# control-zenerbridge2.net
KiCad netlist of a schematic drawn in EAGLE
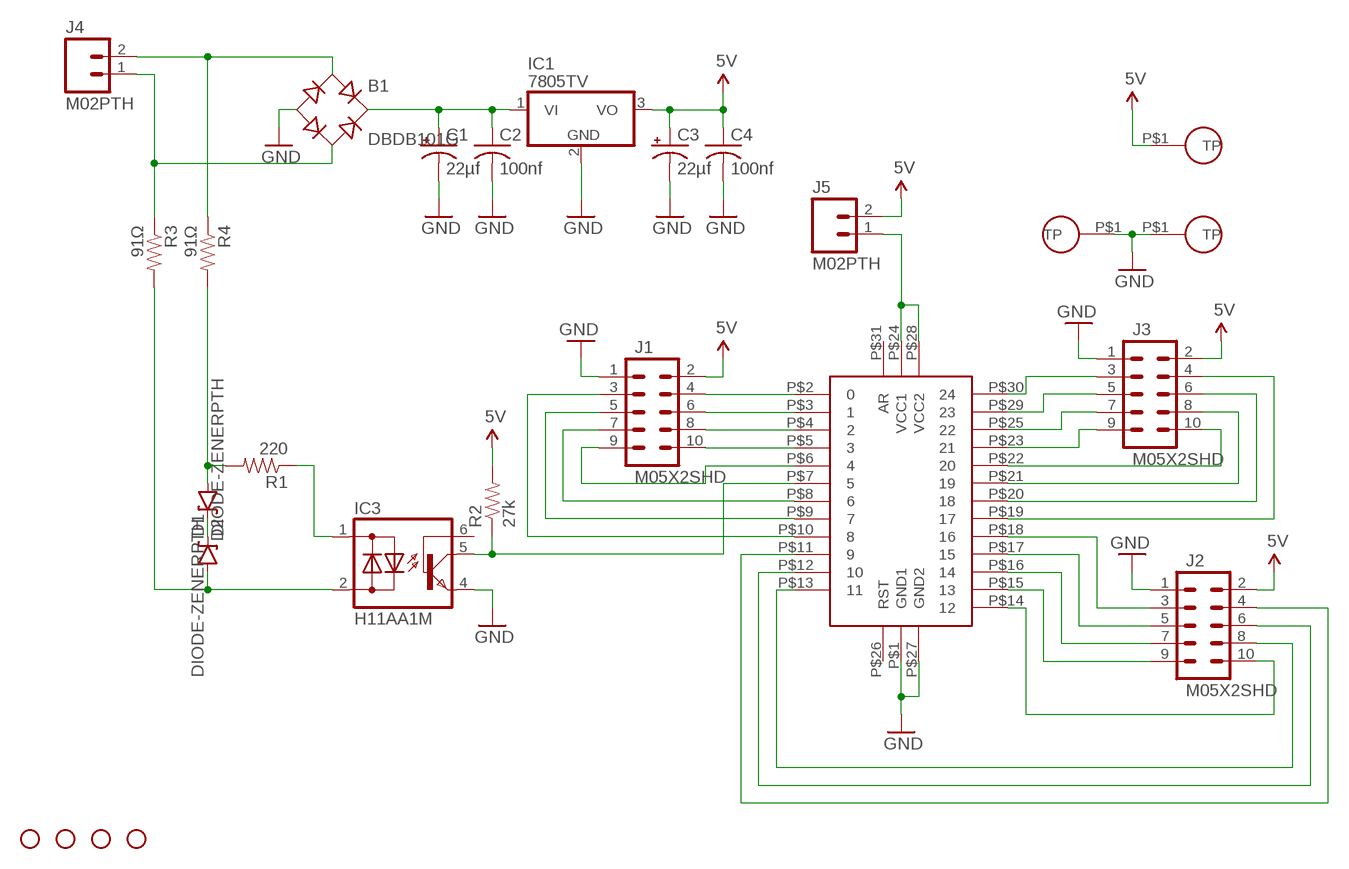
[diagram p0: schematic, sheet 1]

(export (version "E")
  (design (tool "Eeschema 10.0.6"))
  (components
    (comp (ref "B1")
      (value "DBDB101G")
      (footprint "eagle-import:DB")
      (libsource (lib "eagle-import") (part "DB?GDB101"))
    )
    (comp (ref "C1")
      (value "22µf")
      (footprint "eagle-import:E5-8,5")
      (libsource (lib "eagle-import") (part "CPOL-USE5-8.5"))
    )
    (comp (ref "C2")
      (value "100nf")
      (footprint "eagle-import:C025-030X050")
      (libsource (lib "eagle-import") (part "C-US025-030X050"))
    )
    (comp (ref "C3")
      (value "22µf")
      (footprint "eagle-import:E5-8,5")
      (libsource (lib "eagle-import") (part "CPOL-USE5-8.5"))
    )
    (comp (ref "C4")
      (value "100nf")
      (footprint "eagle-import:C025-030X050")
      (libsource (lib "eagle-import") (part "C-US025-030X050"))
    )
    (comp (ref "D1")
      (value "DIODE-ZENERPTH")
      (footprint "eagle-import:DIODE-ZENER")
      (libsource (lib "eagle-import") (part "DIODE-ZENERPTH"))
    )
    (comp (ref "D2")
      (value "DIODE-ZENERPTH")
      (footprint "eagle-import:DIODE-ZENER")
      (libsource (lib "eagle-import") (part "DIODE-ZENERPTH"))
    )
    (comp (ref "IC1")
      (value "7805TV")
      (footprint "eagle-import:TO220V")
      (libsource (lib "eagle-import") (part "78TV05"))
    )
    (comp (ref "IC2")
      (value "TEENSY2")
      (footprint "eagle-import:TEENSY2")
      (libsource (lib "eagle-import") (part "TEENSY2"))
    )
    (comp (ref "IC3")
      (value "H11AA1M")
      (footprint "eagle-import:DIL06")
      (fields (field (name "MF") "Fairchild"))
      (libsource (lib "eagle-import") (part "H11AA1M"))
    )
    (comp (ref "J1")
      (value "M05X2SHD")
      (footprint "eagle-import:2X5-SHROUDED")
      (libsource (lib "eagle-import") (part "M05X2SHD"))
    )
    (comp (ref "J2")
      (value "M05X2SHD")
      (footprint "eagle-import:2X5-SHROUDED")
      (libsource (lib "eagle-import") (part "M05X2SHD"))
    )
    (comp (ref "J3")
      (value "M05X2SHD")
      (footprint "eagle-import:2X5-SHROUDED")
      (libsource (lib "eagle-import") (part "M05X2SHD"))
    )
    (comp (ref "J4")
      (value "M02PTH")
      (footprint "eagle-import:1X02")
      (libsource (lib "eagle-import") (part "M02PTH"))
    )
    (comp (ref "J5")
      (value "M02PTH")
      (footprint "eagle-import:1X02")
      (libsource (lib "eagle-import") (part "M02PTH"))
    )
    (comp (ref "R1")
      (value "220")
      (footprint "eagle-import:AXIAL-0.4")
      (libsource (lib "eagle-import") (part "RESISTORPTH-1/4W"))
    )
    (comp (ref "R2")
      (value "27k")
      (footprint "eagle-import:AXIAL-0.4")
      (libsource (lib "eagle-import") (part "RESISTORPTH-1/4W"))
    )
    (comp (ref "R3")
      (value "91Ω")
      (footprint "eagle-import:AXIAL-0.4")
      (libsource (lib "eagle-import") (part "RESISTORPTH-1/4W"))
    )
    (comp (ref "R4")
      (value "91Ω")
      (footprint "eagle-import:AXIAL-0.4")
      (libsource (lib "eagle-import") (part "RESISTORPTH-1/4W"))
    )
    (comp (ref "STANDOFF1")
      (value "STAND-OFF")
      (footprint "eagle-import:STAND-OFF")
      (libsource (lib "eagle-import") (part "STAND-OFF"))
    )
    (comp (ref "STANDOFF2")
      (value "STAND-OFF")
      (footprint "eagle-import:STAND-OFF")
      (libsource (lib "eagle-import") (part "STAND-OFF"))
    )
    (comp (ref "STANDOFF3")
      (value "STAND-OFF")
      (footprint "eagle-import:STAND-OFF")
      (libsource (lib "eagle-import") (part "STAND-OFF"))
    )
    (comp (ref "STANDOFF4")
      (value "STAND-OFF")
      (footprint "eagle-import:STAND-OFF")
      (libsource (lib "eagle-import") (part "STAND-OFF"))
    )
    (comp (ref "U$3") (value "TP") (footprint "eagle-import:TP") (libsource (lib "eagle-import") (part "TP")))
    (comp (ref "U$8") (value "TP") (footprint "eagle-import:TP") (libsource (lib "eagle-import") (part "TP")))
    (comp (ref "U$9") (value "TP") (footprint "eagle-import:TP") (libsource (lib "eagle-import") (part "TP")))
  )
  (nets
    (net (code "1") (name "5V") (class "Default")
      (node (ref "C3") (pin "+") (pinfunction "+_+") (pintype "passive"))
      (node (ref "C4") (pin "1") (pinfunction "1_1") (pintype "passive"))
      (node (ref "IC1") (pin "3") (pinfunction "VO_3") (pintype "passive"))
      (node (ref "J1") (pin "2") (pinfunction "2_2") (pintype "passive"))
      (node (ref "J2") (pin "2") (pinfunction "2_2") (pintype "passive"))
      (node (ref "J3") (pin "2") (pinfunction "2_2") (pintype "passive"))
      (node (ref "J5") (pin "2") (pinfunction "2_2") (pintype "passive"))
      (node (ref "R2") (pin "P$2") (pinfunction "2_P$2") (pintype "passive"))
      (node (ref "U$8") (pin "P$1") (pinfunction "TP_P$1") (pintype "input"))
    )
    (net (code "2") (name "GND") (class "Default")
      (node (ref "B1") (pin "-") (pinfunction "-_-") (pintype "passive"))
      (node (ref "C1") (pin "-") (pinfunction "-_-") (pintype "passive"))
      (node (ref "C2") (pin "2") (pinfunction "2_2") (pintype "passive"))
      (node (ref "C3") (pin "-") (pinfunction "-_-") (pintype "passive"))
      (node (ref "C4") (pin "2") (pinfunction "2_2") (pintype "passive"))
      (node (ref "IC1") (pin "2") (pinfunction "GND_2") (pintype "passive"))
      (node (ref "IC2") (pin "P$1") (pinfunction "GND1_P$1") (pintype "bidirectional"))
      (node (ref "IC2") (pin "P$27") (pinfunction "GND2_P$27") (pintype "bidirectional"))
      (node (ref "IC3") (pin "4") (pinfunction "E_4") (pintype "passive"))
      (node (ref "J1") (pin "1") (pinfunction "1_1") (pintype "passive"))
      (node (ref "J2") (pin "1") (pinfunction "1_1") (pintype "passive"))
      (node (ref "J3") (pin "1") (pinfunction "1_1") (pintype "passive"))
      (node (ref "U$3") (pin "P$1") (pinfunction "TP_P$1") (pintype "input"))
      (node (ref "U$9") (pin "P$1") (pinfunction "TP_P$1") (pintype "input"))
    )
    (net (code "3") (name "Net-(D1-A)") (class "Default")
      (node (ref "D1") (pin "P$2") (pinfunction "A_P$2") (pintype "passive"))
      (node (ref "IC3") (pin "2") (pinfunction "AC2_2") (pintype "passive"))
      (node (ref "R3") (pin "P$2") (pinfunction "2_P$2") (pintype "passive"))
    )
    (net (code "4") (name "Net-(D1-C)") (class "Default")
      (node (ref "D1") (pin "P$1") (pinfunction "C_P$1") (pintype "passive"))
      (node (ref "D2") (pin "P$1") (pinfunction "C_P$1") (pintype "passive"))
    )
    (net (code "5") (name "Net-(D2-A)") (class "Default")
      (node (ref "D2") (pin "P$2") (pinfunction "A_P$2") (pintype "passive"))
      (node (ref "R1") (pin "P$2") (pinfunction "2_P$2") (pintype "passive"))
      (node (ref "R4") (pin "P$2") (pinfunction "2_P$2") (pintype "passive"))
    )
    (net (code "6") (name "Net-(IC1-VI)") (class "Default")
      (node (ref "B1") (pin "+") (pinfunction "+_+") (pintype "passive"))
      (node (ref "C1") (pin "+") (pinfunction "+_+") (pintype "passive"))
      (node (ref "C2") (pin "1") (pinfunction "1_1") (pintype "passive"))
      (node (ref "IC1") (pin "1") (pinfunction "VI_1") (pintype "input"))
    )
    (net (code "7") (name "Net-(IC2-0)") (class "Default")
      (node (ref "IC2") (pin "P$2") (pinfunction "0_P$2") (pintype "bidirectional"))
      (node (ref "J1") (pin "4") (pinfunction "4_4") (pintype "passive"))
    )
    (net (code "8") (name "Net-(IC2-1)") (class "Default")
      (node (ref "IC2") (pin "P$3") (pinfunction "1_P$3") (pintype "bidirectional"))
      (node (ref "J1") (pin "6") (pinfunction "6_6") (pintype "passive"))
    )
    (net (code "9") (name "Net-(IC2-2)") (class "Default")
      (node (ref "IC2") (pin "P$4") (pinfunction "2_P$4") (pintype "bidirectional"))
      (node (ref "J1") (pin "8") (pinfunction "8_8") (pintype "passive"))
    )
    (net (code "10") (name "Net-(IC2-3)") (class "Default")
      (node (ref "IC2") (pin "P$5") (pinfunction "3_P$5") (pintype "bidirectional"))
      (node (ref "J1") (pin "10") (pinfunction "10_10") (pintype "passive"))
    )
    (net (code "11") (name "Net-(IC2-4)") (class "Default")
      (node (ref "IC2") (pin "P$6") (pinfunction "4_P$6") (pintype "bidirectional"))
      (node (ref "J1") (pin "9") (pinfunction "9_9") (pintype "passive"))
    )
    (net (code "12") (name "Net-(IC2-5)") (class "Default")
      (node (ref "IC2") (pin "P$7") (pinfunction "5_P$7") (pintype "bidirectional"))
      (node (ref "IC3") (pin "5") (pinfunction "C_5") (pintype "passive"))
      (node (ref "R2") (pin "P$1") (pinfunction "1_P$1") (pintype "passive"))
    )
    (net (code "13") (name "Net-(IC2-6)") (class "Default")
      (node (ref "IC2") (pin "P$8") (pinfunction "6_P$8") (pintype "bidirectional"))
      (node (ref "J1") (pin "7") (pinfunction "7_7") (pintype "passive"))
    )
    (net (code "14") (name "Net-(IC2-7)") (class "Default")
      (node (ref "IC2") (pin "P$9") (pinfunction "7_P$9") (pintype "bidirectional"))
      (node (ref "J1") (pin "5") (pinfunction "5_5") (pintype "passive"))
    )
    (net (code "15") (name "Net-(IC2-8)") (class "Default")
      (node (ref "IC2") (pin "P$10") (pinfunction "8_P$10") (pintype "bidirectional"))
      (node (ref "J1") (pin "3") (pinfunction "3_3") (pintype "passive"))
    )
    (net (code "16") (name "Net-(IC2-9)") (class "Default")
      (node (ref "IC2") (pin "P$11") (pinfunction "9_P$11") (pintype "bidirectional"))
      (node (ref "J2") (pin "4") (pinfunction "4_4") (pintype "passive"))
    )
    (net (code "17") (name "Net-(IC2-10)") (class "Default")
      (node (ref "IC2") (pin "P$12") (pinfunction "10_P$12") (pintype "bidirectional"))
      (node (ref "J2") (pin "6") (pinfunction "6_6") (pintype "passive"))
    )
    (net (code "18") (name "Net-(IC2-11)") (class "Default")
      (node (ref "IC2") (pin "P$13") (pinfunction "11_P$13") (pintype "bidirectional"))
      (node (ref "J2") (pin "8") (pinfunction "8_8") (pintype "passive"))
    )
    (net (code "19") (name "Net-(IC2-12)") (class "Default")
      (node (ref "IC2") (pin "P$14") (pinfunction "12_P$14") (pintype "bidirectional"))
      (node (ref "J2") (pin "10") (pinfunction "10_10") (pintype "passive"))
    )
    (net (code "20") (name "Net-(IC2-13)") (class "Default")
      (node (ref "IC2") (pin "P$15") (pinfunction "13_P$15") (pintype "bidirectional"))
      (node (ref "J2") (pin "9") (pinfunction "9_9") (pintype "passive"))
    )
    (net (code "21") (name "Net-(IC2-14)") (class "Default")
      (node (ref "IC2") (pin "P$16") (pinfunction "14_P$16") (pintype "bidirectional"))
      (node (ref "J2") (pin "7") (pinfunction "7_7") (pintype "passive"))
    )
    (net (code "22") (name "Net-(IC2-15)") (class "Default")
      (node (ref "IC2") (pin "P$17") (pinfunction "15_P$17") (pintype "bidirectional"))
      (node (ref "J2") (pin "5") (pinfunction "5_5") (pintype "passive"))
    )
    (net (code "23") (name "Net-(IC2-16)") (class "Default")
      (node (ref "IC2") (pin "P$18") (pinfunction "16_P$18") (pintype "bidirectional"))
      (node (ref "J2") (pin "3") (pinfunction "3_3") (pintype "passive"))
    )
    (net (code "24") (name "Net-(IC2-17)") (class "Default")
      (node (ref "IC2") (pin "P$19") (pinfunction "17_P$19") (pintype "bidirectional"))
      (node (ref "J3") (pin "4") (pinfunction "4_4") (pintype "passive"))
    )
    (net (code "25") (name "Net-(IC2-18)") (class "Default")
      (node (ref "IC2") (pin "P$20") (pinfunction "18_P$20") (pintype "bidirectional"))
      (node (ref "J3") (pin "6") (pinfunction "6_6") (pintype "passive"))
    )
    (net (code "26") (name "Net-(IC2-19)") (class "Default")
      (node (ref "IC2") (pin "P$21") (pinfunction "19_P$21") (pintype "bidirectional"))
      (node (ref "J3") (pin "8") (pinfunction "8_8") (pintype "passive"))
    )
    (net (code "27") (name "Net-(IC2-20)") (class "Default")
      (node (ref "IC2") (pin "P$22") (pinfunction "20_P$22") (pintype "bidirectional"))
      (node (ref "J3") (pin "10") (pinfunction "10_10") (pintype "passive"))
    )
    (net (code "28") (name "Net-(IC2-21)") (class "Default")
      (node (ref "IC2") (pin "P$23") (pinfunction "21_P$23") (pintype "bidirectional"))
      (node (ref "J3") (pin "9") (pinfunction "9_9") (pintype "passive"))
    )
    (net (code "29") (name "Net-(IC2-22)") (class "Default")
      (node (ref "IC2") (pin "P$25") (pinfunction "22_P$25") (pintype "bidirectional"))
      (node (ref "J3") (pin "7") (pinfunction "7_7") (pintype "passive"))
    )
    (net (code "30") (name "Net-(IC2-23)") (class "Default")
      (node (ref "IC2") (pin "P$29") (pinfunction "23_P$29") (pintype "bidirectional"))
      (node (ref "J3") (pin "5") (pinfunction "5_5") (pintype "passive"))
    )
    (net (code "31") (name "Net-(IC2-24)") (class "Default")
      (node (ref "IC2") (pin "P$30") (pinfunction "24_P$30") (pintype "bidirectional"))
      (node (ref "J3") (pin "3") (pinfunction "3_3") (pintype "passive"))
    )
    (net (code "32") (name "Net-(IC2-VCC1)") (class "Default")
      (node (ref "IC2") (pin "P$24") (pinfunction "VCC1_P$24") (pintype "bidirectional"))
      (node (ref "IC2") (pin "P$28") (pinfunction "VCC2_P$28") (pintype "bidirectional"))
      (node (ref "J5") (pin "1") (pinfunction "1_1") (pintype "passive"))
    )
    (net (code "33") (name "Net-(IC3-AC1)") (class "Default")
      (node (ref "IC3") (pin "1") (pinfunction "AC1_1") (pintype "passive"))
      (node (ref "R1") (pin "P$1") (pinfunction "1_P$1") (pintype "passive"))
    )
    (net (code "34") (name "Net-(R3-1)") (class "Default")
      (node (ref "B1") (pin "AC2") (pinfunction "AC2_AC2") (pintype "passive"))
      (node (ref "J4") (pin "1") (pinfunction "1_1") (pintype "passive"))
      (node (ref "R3") (pin "P$1") (pinfunction "1_P$1") (pintype "passive"))
    )
    (net (code "35") (name "Net-(R4-1)") (class "Default")
      (node (ref "B1") (pin "AC1") (pinfunction "AC1_AC1") (pintype "passive"))
      (node (ref "J4") (pin "2") (pinfunction "2_2") (pintype "passive"))
      (node (ref "R4") (pin "P$1") (pinfunction "1_P$1") (pintype "passive"))
    )
    (net (code "36") (name "unconnected-(IC2-AR-PadP$31)") (class "Default")
      (node (ref "IC2") (pin "P$31") (pinfunction "AR_P$31") (pintype "bidirectional"))
    )
    (net (code "37") (name "unconnected-(IC2-RST-PadP$26)") (class "Default")
      (node (ref "IC2") (pin "P$26") (pinfunction "RST_P$26") (pintype "bidirectional"))
    )
    (net (code "38") (name "unconnected-(IC3-B-Pad6)") (class "Default")
      (node (ref "IC3") (pin "6") (pinfunction "B_6") (pintype "passive"))
    )
  )
)
